# RCM-Comm_v3_W.net
KiCad netlist of a schematic drawn in EAGLE
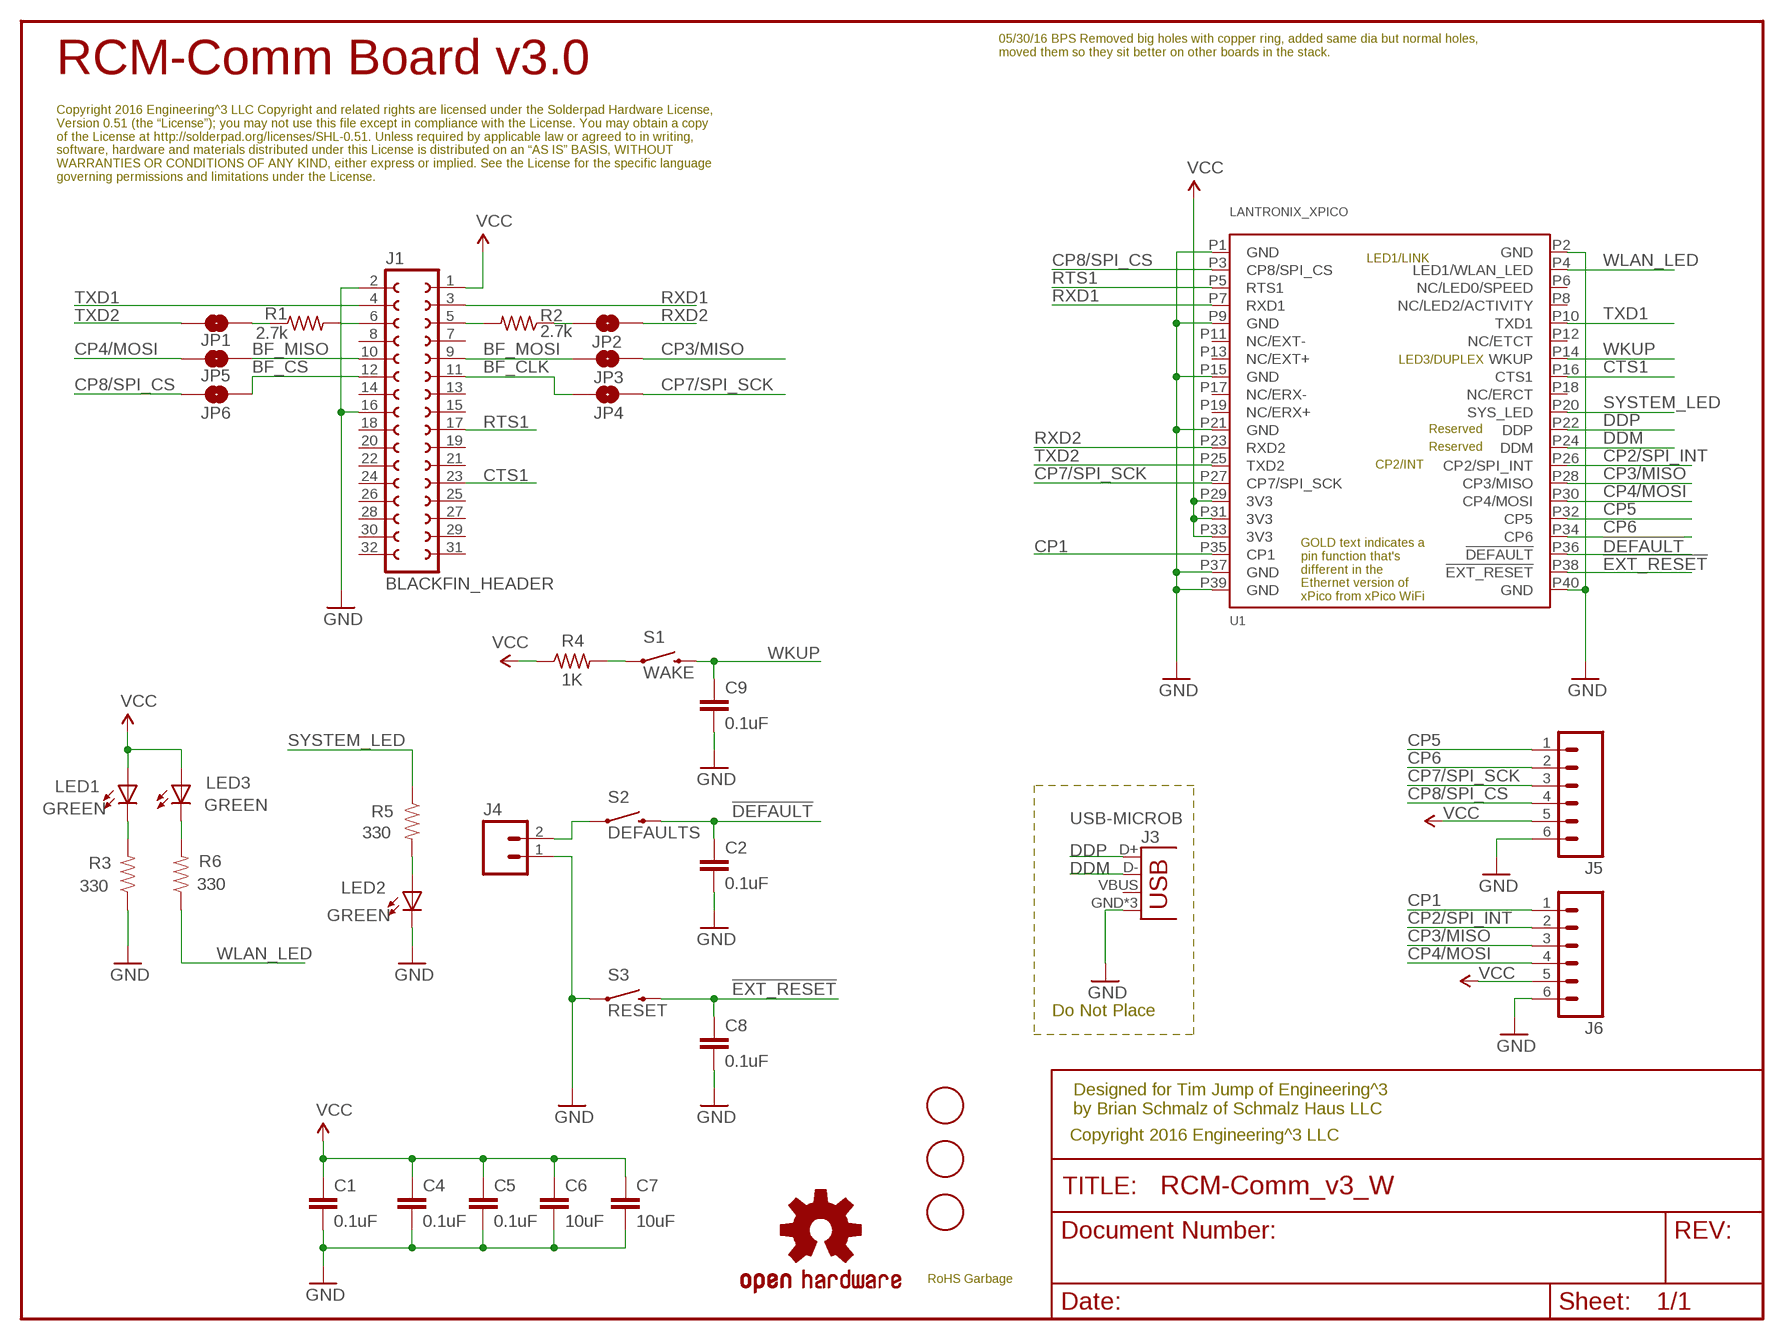
[diagram p0: schematic, sheet 1]

(export (version "E")
  (design (tool "Eeschema 10.0.6"))
  (components
    (comp (ref "C1")
      (value "0.1uF")
      (footprint "eagle-import:0603-CAP")
      (libsource (lib "eagle-import") (part "0.1UF-25V(+80/-20%)(0603)"))
    )
    (comp (ref "C2")
      (value "0.1uF")
      (footprint "eagle-import:0603-CAP")
      (libsource (lib "eagle-import") (part "0.1UF-25V(+80/-20%)(0603)"))
    )
    (comp (ref "C4")
      (value "0.1uF")
      (footprint "eagle-import:0603-CAP")
      (libsource (lib "eagle-import") (part "0.1UF-25V(+80/-20%)(0603)"))
    )
    (comp (ref "C5")
      (value "0.1uF")
      (footprint "eagle-import:0603-CAP")
      (libsource (lib "eagle-import") (part "0.1UF-25V(+80/-20%)(0603)"))
    )
    (comp (ref "C6")
      (value "10uF")
      (footprint "eagle-import:0603-CAP")
      (libsource (lib "eagle-import") (part "10UF-6.3V-20%(0603)"))
    )
    (comp (ref "C7")
      (value "10uF")
      (footprint "eagle-import:0603-CAP")
      (libsource (lib "eagle-import") (part "10UF-6.3V-20%(0603)"))
    )
    (comp (ref "C8")
      (value "0.1uF")
      (footprint "eagle-import:0603-CAP")
      (libsource (lib "eagle-import") (part "0.1UF-25V(+80/-20%)(0603)"))
    )
    (comp (ref "C9")
      (value "0.1uF")
      (footprint "eagle-import:0603-CAP")
      (libsource (lib "eagle-import") (part "0.1UF-25V(+80/-20%)(0603)"))
    )
    (comp (ref "FID1")
      (value "FIDUCIAL")
      (footprint "eagle-import:FIDUCIAL_1MM")
      (libsource (lib "eagle-import") (part "FIDUCIAL"))
    )
    (comp (ref "FID2")
      (value "FIDUCIAL")
      (footprint "eagle-import:FIDUCIAL_1MM")
      (libsource (lib "eagle-import") (part "FIDUCIAL"))
    )
    (comp (ref "FID3")
      (value "FIDUCIAL")
      (footprint "eagle-import:FIDUCIAL_1MM")
      (libsource (lib "eagle-import") (part "FIDUCIAL"))
    )
    (comp (ref "J1")
      (value "BLACKFIN_HEADER")
      (footprint "eagle-import:2X16")
      (libsource (lib "eagle-import") (part "BLACKFIN_HEADER"))
    )
    (comp (ref "J3")
      (value "USB-MICROB")
      (footprint "eagle-import:USB-MICROB")
      (libsource (lib "eagle-import") (part "USB-MICROB"))
    )
    (comp (ref "J4")
      (value "M02LOCK")
      (footprint "eagle-import:1X02_LOCK")
      (libsource (lib "eagle-import") (part "M02LOCK"))
    )
    (comp (ref "J5")
      (value "M06LOCK")
      (footprint "eagle-import:1X06_LOCK")
      (libsource (lib "eagle-import") (part "M06LOCK"))
    )
    (comp (ref "J6")
      (value "M06LOCK")
      (footprint "eagle-import:1X06_LOCK")
      (libsource (lib "eagle-import") (part "M06LOCK"))
    )
    (comp (ref "JP1")
      (value "JUMPER-PAD-2-NOROUND")
      (footprint "eagle-import:PAD-JUMPER-2-NO_YES_SILK_ROUND")
      (libsource (lib "eagle-import") (part "JUMPER-PAD-2-NOROUND"))
    )
    (comp (ref "JP2")
      (value "JUMPER-PAD-2-NOROUND")
      (footprint "eagle-import:PAD-JUMPER-2-NO_YES_SILK_ROUND")
      (libsource (lib "eagle-import") (part "JUMPER-PAD-2-NOROUND"))
    )
    (comp (ref "JP3")
      (value "JUMPER-PAD-2-NOROUND")
      (footprint "eagle-import:PAD-JUMPER-2-NO_YES_SILK_ROUND")
      (libsource (lib "eagle-import") (part "JUMPER-PAD-2-NOROUND"))
    )
    (comp (ref "JP4")
      (value "JUMPER-PAD-2-NOROUND")
      (footprint "eagle-import:PAD-JUMPER-2-NO_YES_SILK_ROUND")
      (libsource (lib "eagle-import") (part "JUMPER-PAD-2-NOROUND"))
    )
    (comp (ref "JP5")
      (value "JUMPER-PAD-2-NOROUND")
      (footprint "eagle-import:PAD-JUMPER-2-NO_YES_SILK_ROUND")
      (libsource (lib "eagle-import") (part "JUMPER-PAD-2-NOROUND"))
    )
    (comp (ref "JP6")
      (value "JUMPER-PAD-2-NOROUND")
      (footprint "eagle-import:PAD-JUMPER-2-NO_YES_SILK_ROUND")
      (libsource (lib "eagle-import") (part "JUMPER-PAD-2-NOROUND"))
    )
    (comp (ref "LED1")
      (value "GREEN")
      (footprint "eagle-import:LED-0603")
      (libsource (lib "eagle-import") (part "LED0603"))
    )
    (comp (ref "LED2")
      (value "GREEN")
      (footprint "eagle-import:LED-0603")
      (libsource (lib "eagle-import") (part "LED0603"))
    )
    (comp (ref "LED3")
      (value "GREEN")
      (footprint "eagle-import:LED-0603")
      (libsource (lib "eagle-import") (part "LED0603"))
    )
    (comp (ref "LOGO1")
      (value "OSHW-LOGOM")
      (footprint "eagle-import:OSHW-LOGO-M")
      (libsource (lib "eagle-import") (part "OSHW-LOGOM"))
    )
    (comp (ref "R1")
      (value "2.7k")
      (footprint "eagle-import:R0603")
      (libsource (lib "eagle-import") (part "R-US_R0603"))
    )
    (comp (ref "R2")
      (value "2.7k")
      (footprint "eagle-import:R0603")
      (libsource (lib "eagle-import") (part "R-US_R0603"))
    )
    (comp (ref "R3")
      (value "330")
      (footprint "eagle-import:0603-RES")
      (libsource (lib "eagle-import") (part "RESISTOR0603-RES"))
    )
    (comp (ref "R4")
      (value "1K")
      (footprint "eagle-import:R0603")
      (libsource (lib "eagle-import") (part "R-US_R0603"))
    )
    (comp (ref "R5")
      (value "330")
      (footprint "eagle-import:0603-RES")
      (libsource (lib "eagle-import") (part "RESISTOR0603-RES"))
    )
    (comp (ref "R6")
      (value "330")
      (footprint "eagle-import:0603-RES")
      (libsource (lib "eagle-import") (part "RESISTOR0603-RES"))
    )
    (comp (ref "S1")
      (value "WAKE")
      (footprint "eagle-import:TACTILE-SWITCH-SMD")
      (libsource (lib "eagle-import") (part "SWITCH-MOMENTARY-2SMD"))
    )
    (comp (ref "S2")
      (value "DEFAULTS")
      (footprint "eagle-import:TACTILE-SWITCH-SMD")
      (libsource (lib "eagle-import") (part "SWITCH-MOMENTARY-2SMD"))
    )
    (comp (ref "S3")
      (value "RESET")
      (footprint "eagle-import:TACTILE-SWITCH-SMD")
      (libsource (lib "eagle-import") (part "SWITCH-MOMENTARY-2SMD"))
    )
    (comp (ref "U$3")
      (value "ROHS_GARBAGE")
      (footprint "eagle-import:ROHS_GARBAGE_5MM")
      (libsource (lib "eagle-import") (part "ROHS_GARBAGE"))
    )
    (comp (ref "U1")
      (value "LANTRONIX_XPICO")
      (footprint "eagle-import:LANTRONIX_XPICO")
      (libsource (lib "eagle-import") (part "LANTRONIX_XPICO"))
    )
  )
  (nets
    (net (code "1") (name "/BF_CLK") (class "Default")
      (node (ref "J1") (pin "11") (pinfunction "SPI_SCK_11") (pintype "passive"))
      (node (ref "JP4") (pin "1") (pinfunction "1_1") (pintype "passive"))
    )
    (net (code "2") (name "/BF_CS") (class "Default")
      (node (ref "J1") (pin "12") (pinfunction "SPI_SEL_12") (pintype "passive"))
      (node (ref "JP6") (pin "2") (pinfunction "2_2") (pintype "passive"))
    )
    (net (code "3") (name "/BF_MISO") (class "Default")
      (node (ref "J1") (pin "10") (pinfunction "SPI_MISO_10") (pintype "passive"))
      (node (ref "JP5") (pin "2") (pinfunction "2_2") (pintype "passive"))
    )
    (net (code "4") (name "/BF_MOSI") (class "Default")
      (node (ref "J1") (pin "9") (pinfunction "SPI_MOSI_9") (pintype "passive"))
      (node (ref "JP3") (pin "1") (pinfunction "1_1") (pintype "passive"))
    )
    (net (code "5") (name "/CP1") (class "Default")
      (node (ref "J6") (pin "1") (pinfunction "1_1") (pintype "passive"))
      (node (ref "U1") (pin "P35") (pinfunction "CP1_P35") (pintype "bidirectional"))
    )
    (net (code "6") (name "/CP2{slash}SPI_INT") (class "Default")
      (node (ref "J6") (pin "2") (pinfunction "2_2") (pintype "passive"))
      (node (ref "U1") (pin "P26") (pinfunction "CP2/SPI_INT_P26") (pintype "bidirectional"))
    )
    (net (code "7") (name "/CP3{slash}MISO") (class "Default")
      (node (ref "J6") (pin "3") (pinfunction "3_3") (pintype "passive"))
      (node (ref "JP3") (pin "2") (pinfunction "2_2") (pintype "passive"))
      (node (ref "U1") (pin "P28") (pinfunction "CP3/MISO_P28") (pintype "bidirectional"))
    )
    (net (code "8") (name "/CP4{slash}MOSI") (class "Default")
      (node (ref "J6") (pin "4") (pinfunction "4_4") (pintype "passive"))
      (node (ref "JP5") (pin "1") (pinfunction "1_1") (pintype "passive"))
      (node (ref "U1") (pin "P30") (pinfunction "CP4/MOSI_P30") (pintype "bidirectional"))
    )
    (net (code "9") (name "/CP5") (class "Default")
      (node (ref "J5") (pin "1") (pinfunction "1_1") (pintype "passive"))
      (node (ref "U1") (pin "P32") (pinfunction "CP5_P32") (pintype "bidirectional"))
    )
    (net (code "10") (name "/CP6") (class "Default")
      (node (ref "J5") (pin "2") (pinfunction "2_2") (pintype "passive"))
      (node (ref "U1") (pin "P34") (pinfunction "CP6_P34") (pintype "bidirectional"))
    )
    (net (code "11") (name "/CP7{slash}SPI_SCK") (class "Default")
      (node (ref "J5") (pin "3") (pinfunction "3_3") (pintype "passive"))
      (node (ref "JP4") (pin "2") (pinfunction "2_2") (pintype "passive"))
      (node (ref "U1") (pin "P27") (pinfunction "CP7/SPI_SCK_P27") (pintype "bidirectional"))
    )
    (net (code "12") (name "/CP8{slash}SPI_CS") (class "Default")
      (node (ref "J5") (pin "4") (pinfunction "4_4") (pintype "passive"))
      (node (ref "JP6") (pin "1") (pinfunction "1_1") (pintype "passive"))
      (node (ref "U1") (pin "P3") (pinfunction "CP8/SPI_CS_P3") (pintype "bidirectional"))
    )
    (net (code "13") (name "/CTS1") (class "Default")
      (node (ref "J1") (pin "23") (pinfunction "GP6_23") (pintype "passive"))
      (node (ref "U1") (pin "P16") (pinfunction "CTS1_P16") (pintype "bidirectional"))
    )
    (net (code "14") (name "/DDM") (class "Default")
      (node (ref "J3") (pin "D-") (pinfunction "D-_D-") (pintype "bidirectional"))
      (node (ref "U1") (pin "P24") (pinfunction "DDM_P24") (pintype "bidirectional"))
    )
    (net (code "15") (name "/DDP") (class "Default")
      (node (ref "J3") (pin "D+") (pinfunction "D+_D+") (pintype "bidirectional"))
      (node (ref "U1") (pin "P22") (pinfunction "DDP_P22") (pintype "bidirectional"))
    )
    (net (code "16") (name "/RTS1") (class "Default")
      (node (ref "J1") (pin "17") (pinfunction "GP0_17") (pintype "passive"))
      (node (ref "U1") (pin "P5") (pinfunction "RTS1_P5") (pintype "bidirectional"))
    )
    (net (code "17") (name "/RXD1") (class "Default")
      (node (ref "J1") (pin "3") (pinfunction "TX0_3") (pintype "passive"))
      (node (ref "U1") (pin "P7") (pinfunction "RXD1_P7") (pintype "bidirectional"))
    )
    (net (code "18") (name "/RXD2") (class "Default")
      (node (ref "JP2") (pin "2") (pinfunction "2_2") (pintype "passive"))
      (node (ref "U1") (pin "P23") (pinfunction "RXD2_P23") (pintype "bidirectional"))
    )
    (net (code "19") (name "/SYSTEM_LED") (class "Default")
      (node (ref "R5") (pin "1") (pinfunction "1_1") (pintype "passive"))
      (node (ref "U1") (pin "P20") (pinfunction "SYS_LED_P20") (pintype "bidirectional"))
    )
    (net (code "20") (name "/TXD1") (class "Default")
      (node (ref "J1") (pin "4") (pinfunction "RX0_4") (pintype "passive"))
      (node (ref "U1") (pin "P10") (pinfunction "TXD1_P10") (pintype "bidirectional"))
    )
    (net (code "21") (name "/TXD2") (class "Default")
      (node (ref "JP1") (pin "1") (pinfunction "1_1") (pintype "passive"))
      (node (ref "U1") (pin "P25") (pinfunction "TXD2_P25") (pintype "bidirectional"))
    )
    (net (code "22") (name "/WKUP") (class "Default")
      (node (ref "C9") (pin "1") (pinfunction "1_1") (pintype "passive"))
      (node (ref "S1") (pin "3") (pinfunction "2_3") (pintype "passive"))
      (node (ref "U1") (pin "P14") (pinfunction "WKUP_P14") (pintype "bidirectional"))
    )
    (net (code "23") (name "/WLAN_LED") (class "Default")
      (node (ref "R6") (pin "1") (pinfunction "1_1") (pintype "passive"))
      (node (ref "U1") (pin "P4") (pinfunction "LED1/WLAN_LED_P4") (pintype "bidirectional"))
    )
    (net (code "24") (name "/~{DEFAULT}") (class "Default")
      (node (ref "C2") (pin "1") (pinfunction "1_1") (pintype "passive"))
      (node (ref "S2") (pin "3") (pinfunction "2_3") (pintype "passive"))
      (node (ref "U1") (pin "P36") (pinfunction "~{DEFAULT}_P36") (pintype "bidirectional"))
    )
    (net (code "25") (name "/~{EXT_RESET}") (class "Default")
      (node (ref "C8") (pin "1") (pinfunction "1_1") (pintype "passive"))
      (node (ref "S3") (pin "3") (pinfunction "2_3") (pintype "passive"))
      (node (ref "U1") (pin "P38") (pinfunction "~{EXT_RESET}_P38") (pintype "bidirectional"))
    )
    (net (code "26") (name "GND") (class "Default")
      (node (ref "C1") (pin "2") (pinfunction "2_2") (pintype "passive"))
      (node (ref "C2") (pin "2") (pinfunction "2_2") (pintype "passive"))
      (node (ref "C4") (pin "2") (pinfunction "2_2") (pintype "passive"))
      (node (ref "C5") (pin "2") (pinfunction "2_2") (pintype "passive"))
      (node (ref "C6") (pin "2") (pinfunction "2_2") (pintype "passive"))
      (node (ref "C7") (pin "2") (pinfunction "2_2") (pintype "passive"))
      (node (ref "C8") (pin "2") (pinfunction "2_2") (pintype "passive"))
      (node (ref "C9") (pin "2") (pinfunction "2_2") (pintype "passive"))
      (node (ref "J1") (pin "16") (pinfunction "GND16_16") (pintype "passive"))
      (node (ref "J1") (pin "2") (pinfunction "GND_2") (pintype "passive"))
      (node (ref "J3") (pin "GND") (pinfunction "GND_GND") (pintype "bidirectional"))
      (node (ref "J3") (pin "MT1") (pinfunction "GND_MT1") (pintype "bidirectional"))
      (node (ref "J3") (pin "MT2") (pinfunction "GND_MT2") (pintype "bidirectional"))
      (node (ref "J4") (pin "1") (pinfunction "1_1") (pintype "passive"))
      (node (ref "J5") (pin "6") (pinfunction "6_6") (pintype "passive"))
      (node (ref "J6") (pin "6") (pinfunction "6_6") (pintype "passive"))
      (node (ref "LED2") (pin "C") (pinfunction "C_C") (pintype "passive"))
      (node (ref "R3") (pin "1") (pinfunction "1_1") (pintype "passive"))
      (node (ref "S3") (pin "1") (pinfunction "1_1") (pintype "passive"))
      (node (ref "U1") (pin "P1") (pinfunction "GND_P1") (pintype "bidirectional"))
      (node (ref "U1") (pin "P15") (pinfunction "GND_P15") (pintype "bidirectional"))
      (node (ref "U1") (pin "P2") (pinfunction "GND_P2") (pintype "bidirectional"))
      (node (ref "U1") (pin "P21") (pinfunction "GND_P21") (pintype "bidirectional"))
      (node (ref "U1") (pin "P37") (pinfunction "GND_P37") (pintype "bidirectional"))
      (node (ref "U1") (pin "P39") (pinfunction "GND_P39") (pintype "bidirectional"))
      (node (ref "U1") (pin "P40") (pinfunction "GND_P40") (pintype "bidirectional"))
      (node (ref "U1") (pin "P9") (pinfunction "GND_P9") (pintype "bidirectional"))
    )
    (net (code "27") (name "Net-(J1-RX1)") (class "Default")
      (node (ref "J1") (pin "6") (pinfunction "RX1_6") (pintype "passive"))
      (node (ref "R1") (pin "2") (pinfunction "2_2") (pintype "passive"))
    )
    (net (code "28") (name "Net-(J1-TX1)") (class "Default")
      (node (ref "J1") (pin "5") (pinfunction "TX1_5") (pintype "passive"))
      (node (ref "R2") (pin "2") (pinfunction "2_2") (pintype "passive"))
    )
    (net (code "29") (name "Net-(J4-Pad2)") (class "Default")
      (node (ref "J4") (pin "2") (pinfunction "2_2") (pintype "passive"))
      (node (ref "S2") (pin "1") (pinfunction "1_1") (pintype "passive"))
    )
    (net (code "30") (name "Net-(JP1-Pad2)") (class "Default")
      (node (ref "JP1") (pin "2") (pinfunction "2_2") (pintype "passive"))
      (node (ref "R1") (pin "1") (pinfunction "1_1") (pintype "passive"))
    )
    (net (code "31") (name "Net-(JP2-Pad1)") (class "Default")
      (node (ref "JP2") (pin "1") (pinfunction "1_1") (pintype "passive"))
      (node (ref "R2") (pin "1") (pinfunction "1_1") (pintype "passive"))
    )
    (net (code "32") (name "Net-(LED1-PadC)") (class "Default")
      (node (ref "LED1") (pin "C") (pinfunction "C_C") (pintype "passive"))
      (node (ref "R3") (pin "2") (pinfunction "2_2") (pintype "passive"))
    )
    (net (code "33") (name "Net-(LED2-PadA)") (class "Default")
      (node (ref "LED2") (pin "A") (pinfunction "A_A") (pintype "passive"))
      (node (ref "R5") (pin "2") (pinfunction "2_2") (pintype "passive"))
    )
    (net (code "34") (name "Net-(LED3-PadC)") (class "Default")
      (node (ref "LED3") (pin "C") (pinfunction "C_C") (pintype "passive"))
      (node (ref "R6") (pin "2") (pinfunction "2_2") (pintype "passive"))
    )
    (net (code "35") (name "Net-(R4-Pad2)") (class "Default")
      (node (ref "R4") (pin "2") (pinfunction "2_2") (pintype "passive"))
      (node (ref "S1") (pin "1") (pinfunction "1_1") (pintype "passive"))
    )
    (net (code "36") (name "VCC") (class "Default")
      (node (ref "C1") (pin "1") (pinfunction "1_1") (pintype "passive"))
      (node (ref "C4") (pin "1") (pinfunction "1_1") (pintype "passive"))
      (node (ref "C5") (pin "1") (pinfunction "1_1") (pintype "passive"))
      (node (ref "C6") (pin "1") (pinfunction "1_1") (pintype "passive"))
      (node (ref "C7") (pin "1") (pinfunction "1_1") (pintype "passive"))
      (node (ref "J1") (pin "1") (pinfunction "3.3V_1") (pintype "passive"))
      (node (ref "J5") (pin "5") (pinfunction "5_5") (pintype "passive"))
      (node (ref "J6") (pin "5") (pinfunction "5_5") (pintype "passive"))
      (node (ref "LED1") (pin "A") (pinfunction "A_A") (pintype "passive"))
      (node (ref "LED3") (pin "A") (pinfunction "A_A") (pintype "passive"))
      (node (ref "R4") (pin "1") (pinfunction "1_1") (pintype "passive"))
      (node (ref "U1") (pin "P29") (pinfunction "3V3_P29") (pintype "bidirectional"))
      (node (ref "U1") (pin "P31") (pinfunction "3V3_P31") (pintype "bidirectional"))
      (node (ref "U1") (pin "P33") (pinfunction "3V3_P33") (pintype "bidirectional"))
    )
    (net (code "37") (name "unconnected-(J1-GP1-Pad18)") (class "Default")
      (node (ref "J1") (pin "18") (pinfunction "GP1_18") (pintype "passive"))
    )
    (net (code "38") (name "unconnected-(J1-GP2-Pad19)") (class "Default")
      (node (ref "J1") (pin "19") (pinfunction "GP2_19") (pintype "passive"))
    )
    (net (code "39") (name "unconnected-(J1-GP3-Pad20)") (class "Default")
      (node (ref "J1") (pin "20") (pinfunction "GP3_20") (pintype "passive"))
    )
    (net (code "40") (name "unconnected-(J1-GP4-Pad21)") (class "Default")
      (node (ref "J1") (pin "21") (pinfunction "GP4_21") (pintype "passive"))
    )
    (net (code "41") (name "unconnected-(J1-GP5-Pad22)") (class "Default")
      (node (ref "J1") (pin "22") (pinfunction "GP5_22") (pintype "passive"))
    )
    (net (code "42") (name "unconnected-(J1-GP7-Pad24)") (class "Default")
      (node (ref "J1") (pin "24") (pinfunction "GP7_24") (pintype "passive"))
    )
    (net (code "43") (name "unconnected-(J1-GP8-Pad25)") (class "Default")
      (node (ref "J1") (pin "25") (pinfunction "GP8_25") (pintype "passive"))
    )
    (net (code "44") (name "unconnected-(J1-GP9-Pad26)") (class "Default")
      (node (ref "J1") (pin "26") (pinfunction "GP9_26") (pintype "passive"))
    )
    (net (code "45") (name "unconnected-(J1-GPA-Pad27)") (class "Default")
      (node (ref "J1") (pin "27") (pinfunction "GPA_27") (pintype "passive"))
    )
    (net (code "46") (name "unconnected-(J1-GPB-Pad28)") (class "Default")
      (node (ref "J1") (pin "28") (pinfunction "GPB_28") (pintype "passive"))
    )
    (net (code "47") (name "unconnected-(J1-GPC-Pad29)") (class "Default")
      (node (ref "J1") (pin "29") (pinfunction "GPC_29") (pintype "passive"))
    )
    (net (code "48") (name "unconnected-(J1-GPD-Pad30)") (class "Default")
      (node (ref "J1") (pin "30") (pinfunction "GPD_30") (pintype "passive"))
    )
    (net (code "49") (name "unconnected-(J1-GPE-Pad31)") (class "Default")
      (node (ref "J1") (pin "31") (pinfunction "GPE_31") (pintype "passive"))
    )
    (net (code "50") (name "unconnected-(J1-GPF-Pad32)") (class "Default")
      (node (ref "J1") (pin "32") (pinfunction "GPF_32") (pintype "passive"))
    )
    (net (code "51") (name "unconnected-(J1-I2C_SDA-Pad15)") (class "Default")
      (node (ref "J1") (pin "15") (pinfunction "I2C_SDA_15") (pintype "passive"))
    )
    (net (code "52") (name "unconnected-(J1-SPI_SCL-Pad14)") (class "Default")
      (node (ref "J1") (pin "14") (pinfunction "SPI_SCL_14") (pintype "passive"))
    )
    (net (code "53") (name "unconnected-(J1-SPI_SEL2-Pad13)") (class "Default")
      (node (ref "J1") (pin "13") (pinfunction "SPI_SEL2_13") (pintype "passive"))
    )
    (net (code "54") (name "unconnected-(J1-TMR2-Pad7)") (class "Default")
      (node (ref "J1") (pin "7") (pinfunction "TMR2_7") (pintype "passive"))
    )
    (net (code "55") (name "unconnected-(J1-TMR3-Pad8)") (class "Default")
      (node (ref "J1") (pin "8") (pinfunction "TMR3_8") (pintype "passive"))
    )
    (net (code "56") (name "unconnected-(J3-PadVBUS)") (class "Default")
      (node (ref "J3") (pin "VBUS") (pinfunction "VBUS_VBUS") (pintype "bidirectional"))
    )
    (net (code "57") (name "unconnected-(U1-NC{slash}ERCT-PadP18)") (class "Default")
      (node (ref "U1") (pin "P18") (pinfunction "NC/ERCT_P18") (pintype "bidirectional"))
    )
    (net (code "58") (name "unconnected-(U1-NC{slash}ERX+-PadP19)") (class "Default")
      (node (ref "U1") (pin "P19") (pinfunction "NC/ERX+_P19") (pintype "bidirectional"))
    )
    (net (code "59") (name "unconnected-(U1-NC{slash}ERX--PadP17)") (class "Default")
      (node (ref "U1") (pin "P17") (pinfunction "NC/ERX-_P17") (pintype "bidirectional"))
    )
    (net (code "60") (name "unconnected-(U1-NC{slash}ETCT-PadP12)") (class "Default")
      (node (ref "U1") (pin "P12") (pinfunction "NC/ETCT_P12") (pintype "bidirectional"))
    )
    (net (code "61") (name "unconnected-(U1-NC{slash}EXT+-PadP13)") (class "Default")
      (node (ref "U1") (pin "P13") (pinfunction "NC/EXT+_P13") (pintype "bidirectional"))
    )
    (net (code "62") (name "unconnected-(U1-NC{slash}EXT--PadP11)") (class "Default")
      (node (ref "U1") (pin "P11") (pinfunction "NC/EXT-_P11") (pintype "bidirectional"))
    )
    (net (code "63") (name "unconnected-(U1-NC{slash}LED0{slash}SPEED-PadP6)") (class "Default")
      (node (ref "U1") (pin "P6") (pinfunction "NC/LED0/SPEED_P6") (pintype "bidirectional"))
    )
    (net (code "64") (name "unconnected-(U1-NC{slash}LED2{slash}ACTIVITY-PadP8)") (class "Default")
      (node (ref "U1") (pin "P8") (pinfunction "NC/LED2/ACTIVITY_P8") (pintype "bidirectional"))
    )
  )
)
